# schematic.net
KiCad netlist of a schematic drawn in Altium Designer
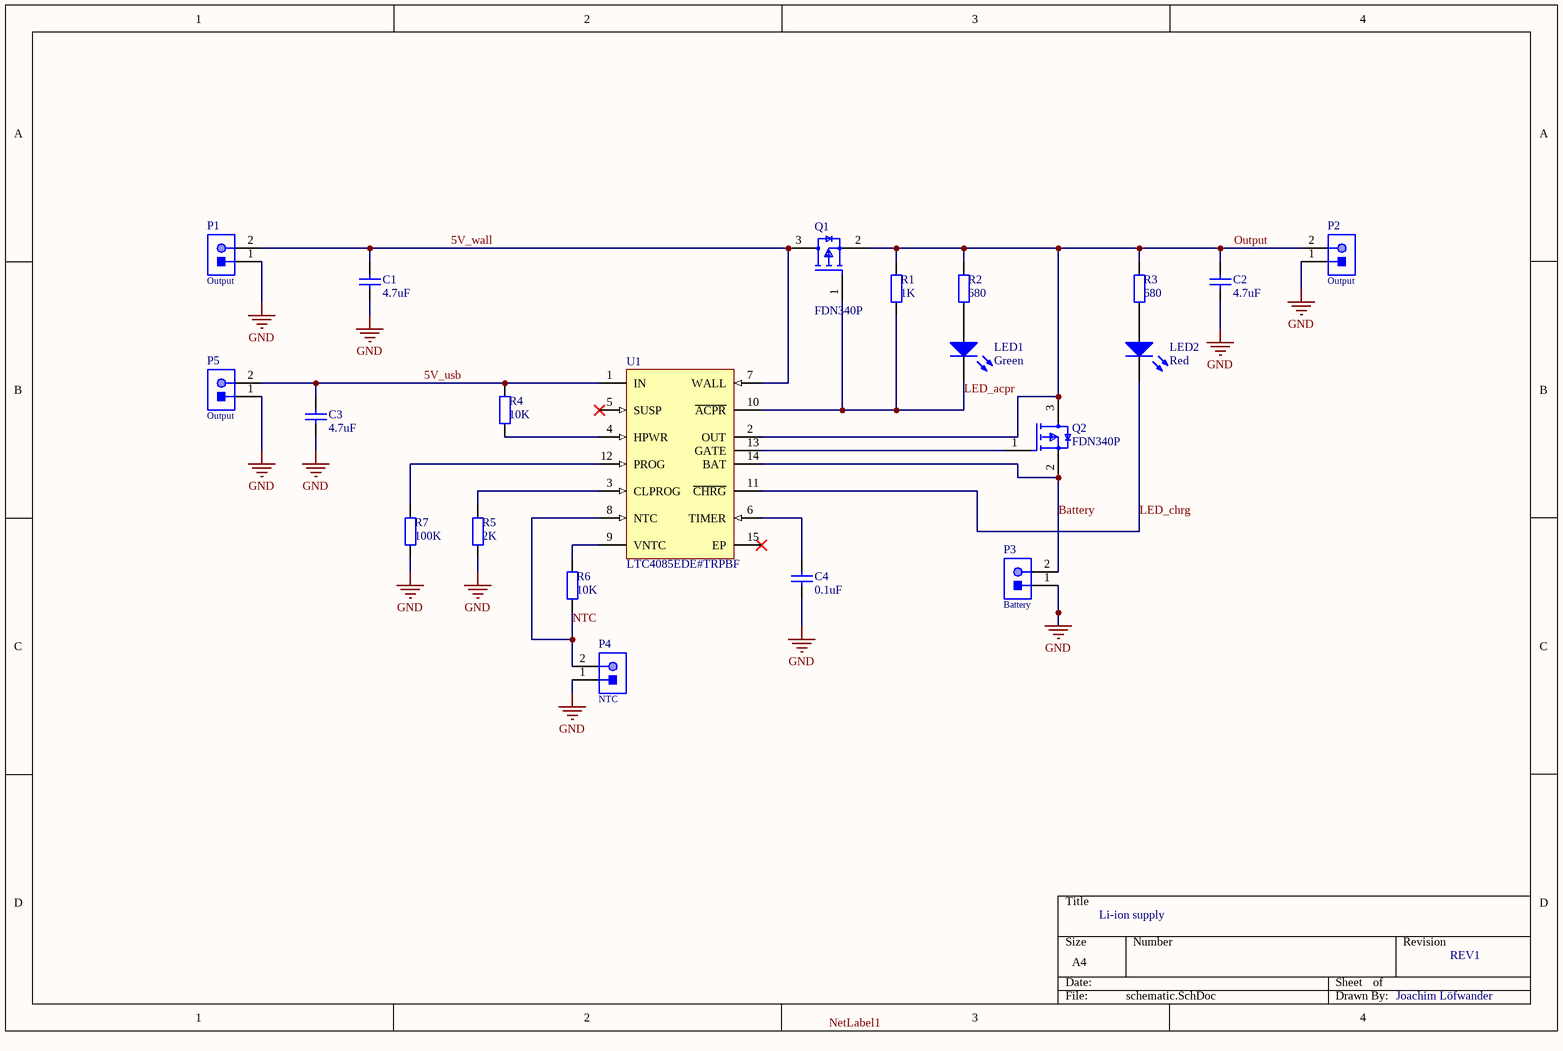
[diagram p0: schematic.SchDoc]

(export (version "E")
  (design (tool "Eeschema 10.0.6"))
  (components
    (comp (ref "C1")
      (value "4.7uF")
      (footprint "CAPC2013X145X50ML20T25")
      (fields (field (name "MANUFACTURER") "Kemet") (field (name "PART NUMBER") "C0805C475K3PACTU"))
      (libsource (lib "Altium Content Vault") (part "CAP"))
    )
    (comp (ref "C2")
      (value "4.7uF")
      (footprint "CAPC2013X145X50ML20T25")
      (fields (field (name "MANUFACTURER") "Kemet") (field (name "PART NUMBER") "C0805C475K3PACTU"))
      (libsource (lib "Altium Content Vault") (part "CAP"))
    )
    (comp (ref "C3")
      (value "4.7uF")
      (footprint "CAPC2013X145X50ML20T25")
      (fields (field (name "MANUFACTURER") "Kemet") (field (name "PART NUMBER") "C0805C475K3PACTU"))
      (libsource (lib "Altium Content Vault") (part "CAP"))
    )
    (comp (ref "C4")
      (value "0.1uF")
      (footprint "CAPC2013X135X45ML10T25")
      (description "Chip Capacitor, 0.1 uF, +/- 10%, 50 V, -55 to 125 degC, 0805 (2012 Metric), RoHS, Tape and Reel")
      (fields (field (name "VOLTAGE") "50V") (field (name "TOLERANCE") "10%"))
      (libsource (lib "Altium Content Vault") (part "CAP-NP-2"))
    )
    (comp (ref "LED1")
      (value "Green")
      (footprint "0805_A")
      (description "SMD mono-color Chip LED, WL-SMCW, Green")
      (fields (field (name "PARTNUMBER") "150080GS75000") (field (name "MANUFACTURER") "Wuerth Elektronik"))
      (libsource (lib "Altium Content Vault") (part "WE-LED_K1A2-2"))
    )
    (comp (ref "LED2")
      (value "Red")
      (footprint "0805_A")
      (description "SMD mono-color Chip LED, WL-SMCW, Red")
      (fields (field (name "PARTNUMBER") "150080RS75000") (field (name "MANUFACTURER") "Wuerth Elektronik"))
      (libsource (lib "Altium Content Vault") (part "WE-LED_K1A2-2"))
    )
    (comp (ref "P1")
      (value "Output")
      (footprint "61300211121")
      (description "THT Vertical Pin Header WR-PHD, Pitch 2.54 mm, Single Row, 2 pins")
      (fields
        (field (name "MANUFACTURER") "Wurth Elektronik")
        (field (name "PART NUMBER") "61300211121")
        (field (name "PUBLISHER") "WurthElektronik")
      )
      (libsource (lib "Altium Content Vault") (part "WE-CN-1P-M-R2"))
    )
    (comp (ref "P2")
      (value "Output")
      (footprint "61300211121")
      (description "THT Vertical Pin Header WR-PHD, Pitch 2.54 mm, Single Row, 2 pins")
      (fields
        (field (name "MANUFACTURER") "Wurth Elektronik")
        (field (name "PART NUMBER") "61300211121")
        (field (name "PUBLISHER") "WurthElektronik")
      )
      (libsource (lib "") (part "WE-CN-1P-M-R2_1"))
    )
    (comp (ref "P3")
      (value "Battery")
      (footprint "61300211121")
      (description "THT Vertical Pin Header WR-PHD, Pitch 2.54 mm, Single Row, 2 pins")
      (fields
        (field (name "MANUFACTURER") "Wurth Elektronik")
        (field (name "PART NUMBER") "61300211121")
        (field (name "PUBLISHER") "WurthElektronik")
      )
      (libsource (lib "Altium Content Vault") (part "WE-CN-1P-M-R2"))
    )
    (comp (ref "P4")
      (value "NTC")
      (footprint "61300211121")
      (description "THT Vertical Pin Header WR-PHD, Pitch 2.54 mm, Single Row, 2 pins")
      (fields
        (field (name "MANUFACTURER") "Wurth Elektronik")
        (field (name "PART NUMBER") "61300211121")
        (field (name "PUBLISHER") "WurthElektronik")
      )
      (libsource (lib "") (part "WE-CN-1P-M-R2_1"))
    )
    (comp (ref "P5")
      (value "Output")
      (footprint "61300211121")
      (description "THT Vertical Pin Header WR-PHD, Pitch 2.54 mm, Single Row, 2 pins")
      (fields
        (field (name "MANUFACTURER") "Wurth Elektronik")
        (field (name "PART NUMBER") "61300211121")
        (field (name "PUBLISHER") "WurthElektronik")
      )
      (libsource (lib "Altium Content Vault") (part "WE-CN-1P-M-R2"))
    )
    (comp (ref "Q1")
      (value "FDN340P")
      (footprint "FP-527AG-MFG")
      (description "MOSFET P-CH 20V 2A SSOT3")
      (libsource (lib "Altium Content Vault") (part "d23f43cc42f60b967b7caccf14518fd"))
    )
    (comp (ref "Q2")
      (value "FDN340P")
      (footprint "FP-527AG-MFG")
      (description "MOSFET P-CH 20V 2A SSOT3")
      (libsource (lib "Altium Content Vault") (part "d23f43cc42f60b967b7caccf14518fd"))
    )
    (comp (ref "R1")
      (value "1K")
      (footprint "RESC2013X50X30ML20T20")
      (fields (field (name "PART NUMBER") "CRCW08051K00FKEA") (field (name "MANUFACTURER") "Vishay Dale"))
      (libsource (lib "Altium Content Vault") (part "RES"))
    )
    (comp (ref "R2")
      (value "680")
      (footprint "RESC2013X50X30ML20T20")
      (fields (field (name "MANUFACTURER") "Vishay Dale") (field (name "PART NUMBER") "CRCW0805680RFKEA"))
      (libsource (lib "Altium Content Vault") (part "RES"))
    )
    (comp (ref "R3")
      (value "680")
      (footprint "RESC2013X50X30ML20T20")
      (fields (field (name "MANUFACTURER") "Vishay Dale") (field (name "PART NUMBER") "CRCW0805680RFKEA"))
      (libsource (lib "Altium Content Vault") (part "RES"))
    )
    (comp (ref "R4")
      (value "10K")
      (footprint "RESC2013X70X40ML20T20")
      (fields (field (name "PART NUMBER") "ERJ-6GEYJ103V") (field (name "MANUFACTURER") "Panasonic"))
      (libsource (lib "Altium Content Vault") (part "RES"))
    )
    (comp (ref "R5")
      (value "2K")
      (footprint "RESC2013X60X35ML10T20")
      (fields (field (name "MANUFACTURER") "Yageo") (field (name "PART NUMBER") "RC0805JR-072KL"))
      (libsource (lib "Altium Content Vault") (part "RES"))
    )
    (comp (ref "R6")
      (value "10K")
      (footprint "RESC2012X145X30ML20T15")
      (fields (field (name "MANUFACTURER") "Vishay Dale") (field (name "PART NUMBER") "NTHS0805N02N1002JE"))
      (libsource (lib "Altium Content Vault") (part "RES"))
    )
    (comp (ref "R7")
      (value "100K")
      (footprint "RESC2013X70X40ML20T20")
      (fields (field (name "PART NUMBER") "ERJ-6GEYJ104V") (field (name "MANUFACTURER") "Panasonic"))
      (libsource (lib "Altium Content Vault") (part "RES"))
    )
    (comp (ref "U1")
      (value "LTC4085EDE#TRPBF")
      (footprint "LT-DE-14_V")
      (fields (field (name "MANUFACTURER") "Linear Technology"))
      (libsource (lib "Altium Content Vault") (part "LT-LTC4085-DE-14"))
    )
  )
  (nets
    (net (code "1") (name "/5V_usb") (class "Default")
      (node (ref "C3") (pin "2") (pinfunction "2_2") (pintype "passive"))
      (node (ref "P5") (pin "2") (pinfunction "2_2") (pintype "passive"))
      (node (ref "R4") (pin "2") (pinfunction "2_2") (pintype "passive"))
      (node (ref "U1") (pin "1") (pinfunction "IN_1") (pintype "power_in"))
    )
    (net (code "2") (name "/5V_wall") (class "Default")
      (node (ref "C1") (pin "2") (pinfunction "2_2") (pintype "passive"))
      (node (ref "P1") (pin "2") (pinfunction "2_2") (pintype "passive"))
      (node (ref "Q1") (pin "3") (pinfunction "D_3") (pintype "passive"))
      (node (ref "U1") (pin "7") (pinfunction "WALL_7") (pintype "input"))
    )
    (net (code "3") (name "/Battery") (class "Default")
      (node (ref "P3") (pin "2") (pinfunction "2_2") (pintype "passive"))
      (node (ref "Q2") (pin "2") (pinfunction "S_2") (pintype "passive"))
      (node (ref "U1") (pin "14") (pinfunction "BAT_14") (pintype "power_in"))
    )
    (net (code "4") (name "/LED_acpr") (class "Default")
      (node (ref "LED1") (pin "1") (pinfunction "K_1") (pintype "passive"))
      (node (ref "Q1") (pin "1") (pinfunction "G_1") (pintype "passive"))
      (node (ref "R1") (pin "1") (pinfunction "1_1") (pintype "passive"))
      (node (ref "U1") (pin "10") (pinfunction "~{ACPR}_10") (pintype "tri_state"))
    )
    (net (code "5") (name "/LED_chrg") (class "Default")
      (node (ref "LED2") (pin "1") (pinfunction "K_1") (pintype "passive"))
      (node (ref "U1") (pin "11") (pinfunction "~{CHRG}_11") (pintype "tri_state"))
    )
    (net (code "6") (name "/NTC") (class "Default")
      (node (ref "P4") (pin "2") (pinfunction "2_2") (pintype "passive"))
      (node (ref "R6") (pin "1") (pinfunction "1_1") (pintype "passive"))
      (node (ref "U1") (pin "8") (pinfunction "NTC_8") (pintype "input"))
    )
    (net (code "8") (name "/Output") (class "Default")
      (node (ref "C2") (pin "2") (pinfunction "2_2") (pintype "passive"))
      (node (ref "P2") (pin "2") (pinfunction "2_2") (pintype "passive"))
      (node (ref "Q1") (pin "2") (pinfunction "S_2") (pintype "passive"))
      (node (ref "Q2") (pin "3") (pinfunction "D_3") (pintype "passive"))
      (node (ref "R1") (pin "2") (pinfunction "2_2") (pintype "passive"))
      (node (ref "R2") (pin "2") (pinfunction "2_2") (pintype "passive"))
      (node (ref "R3") (pin "2") (pinfunction "2_2") (pintype "passive"))
      (node (ref "U1") (pin "2") (pinfunction "OUT_2") (pintype "power_in"))
    )
    (net (code "9") (name "GND") (class "Default")
      (node (ref "C1") (pin "1") (pinfunction "1_1") (pintype "passive"))
      (node (ref "C2") (pin "1") (pinfunction "1_1") (pintype "passive"))
      (node (ref "C3") (pin "1") (pinfunction "1_1") (pintype "passive"))
      (node (ref "C4") (pin "1") (pinfunction "1_1") (pintype "passive"))
      (node (ref "P1") (pin "1") (pinfunction "1_1") (pintype "passive"))
      (node (ref "P2") (pin "1") (pinfunction "1_1") (pintype "passive"))
      (node (ref "P3") (pin "1") (pinfunction "1_1") (pintype "passive"))
      (node (ref "P4") (pin "1") (pinfunction "1_1") (pintype "passive"))
      (node (ref "P5") (pin "1") (pinfunction "1_1") (pintype "passive"))
      (node (ref "R5") (pin "1") (pinfunction "1_1") (pintype "passive"))
      (node (ref "R7") (pin "1") (pinfunction "1_1") (pintype "passive"))
    )
    (net (code "10") (name "Net-(LED1-A)") (class "Default")
      (node (ref "LED1") (pin "2") (pinfunction "A_2") (pintype "passive"))
      (node (ref "R2") (pin "1") (pinfunction "1_1") (pintype "passive"))
    )
    (net (code "11") (name "Net-(LED2-A)") (class "Default")
      (node (ref "LED2") (pin "2") (pinfunction "A_2") (pintype "passive"))
      (node (ref "R3") (pin "1") (pinfunction "1_1") (pintype "passive"))
    )
    (net (code "12") (name "Net-(Q2-G)") (class "Default")
      (node (ref "Q2") (pin "1") (pinfunction "G_1") (pintype "passive"))
      (node (ref "U1") (pin "13") (pinfunction "GATE_13") (pintype "tri_state"))
    )
    (net (code "13") (name "Net-(U1-CLPROG)") (class "Default")
      (node (ref "R5") (pin "2") (pinfunction "2_2") (pintype "passive"))
      (node (ref "U1") (pin "3") (pinfunction "CLPROG_3") (pintype "input"))
    )
    (net (code "14") (name "Net-(U1-HPWR)") (class "Default")
      (node (ref "R4") (pin "1") (pinfunction "1_1") (pintype "passive"))
      (node (ref "U1") (pin "4") (pinfunction "HPWR_4") (pintype "input"))
    )
    (net (code "15") (name "Net-(U1-PROG)") (class "Default")
      (node (ref "R7") (pin "2") (pinfunction "2_2") (pintype "passive"))
      (node (ref "U1") (pin "12") (pinfunction "PROG_12") (pintype "input"))
    )
    (net (code "16") (name "Net-(U1-TIMER)") (class "Default")
      (node (ref "C4") (pin "2") (pinfunction "2_2") (pintype "passive"))
      (node (ref "U1") (pin "6") (pinfunction "TIMER_6") (pintype "input"))
    )
    (net (code "17") (name "Net-(U1-VNTC)") (class "Default")
      (node (ref "R6") (pin "2") (pinfunction "2_2") (pintype "passive"))
      (node (ref "U1") (pin "9") (pinfunction "VNTC_9") (pintype "passive"))
    )
    (net (code "18") (name "unconnected-(U1-EP-Pad15)") (class "Default")
      (node (ref "U1") (pin "15") (pinfunction "EP_15") (pintype "power_in+no_connect"))
    )
    (net (code "19") (name "unconnected-(U1-SUSP-Pad5)") (class "Default")
      (node (ref "U1") (pin "5") (pinfunction "SUSP_5") (pintype "input+no_connect"))
    )
  )
)
